# UsbPowerSupply.net
KiCad netlist of a schematic drawn in EAGLE
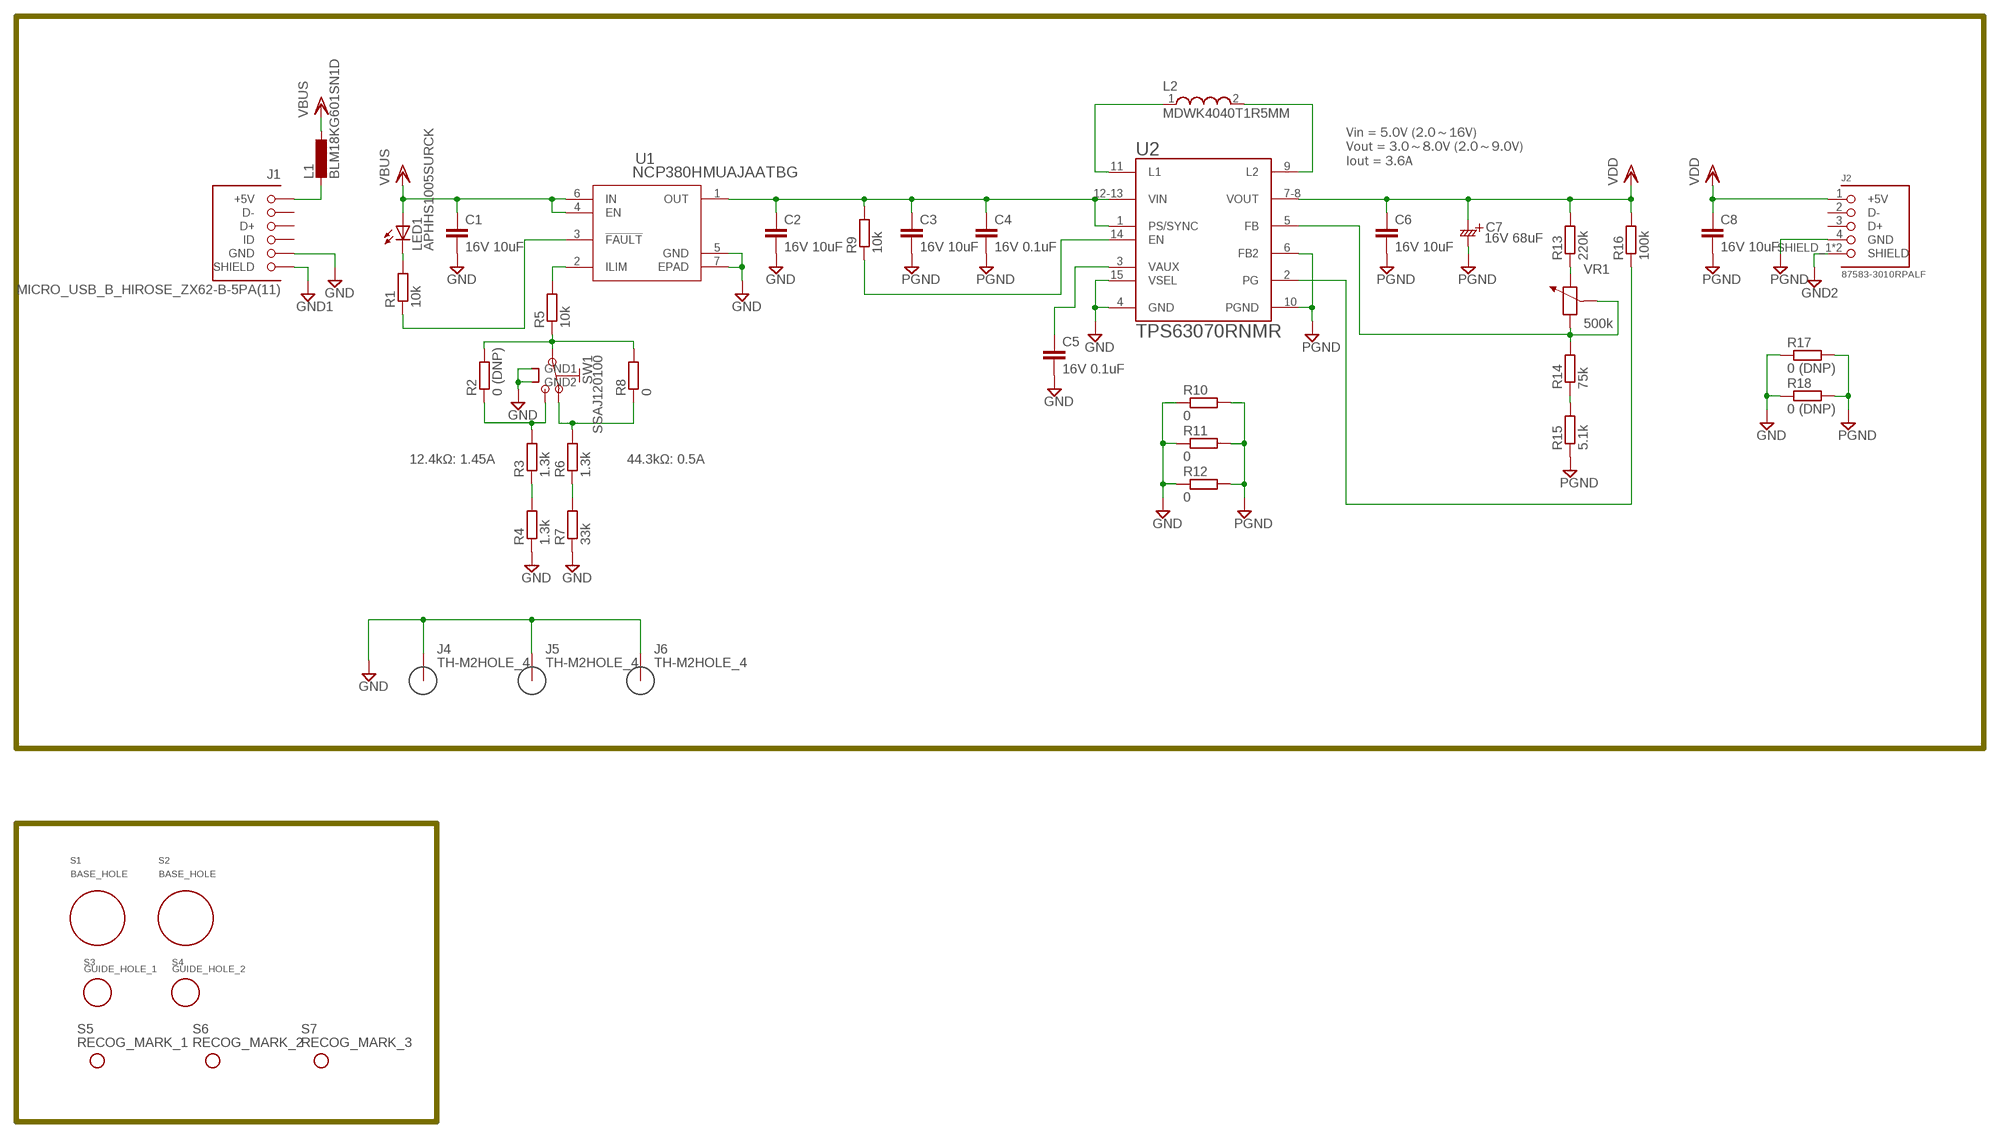
[diagram p0: schematic, sheet 1]

(export (version "E")
  (design (tool "Eeschema 10.0.6"))
  (components
    (comp (ref "C1")
      (value "16V 10uF")
      (footprint "eagle-import:C0603M")
      (libsource (lib "eagle-import") (part "C-EUC0603M"))
    )
    (comp (ref "C2")
      (value "16V 10uF")
      (footprint "eagle-import:C0603M")
      (libsource (lib "eagle-import") (part "C-EUC0603M"))
    )
    (comp (ref "C3")
      (value "16V 10uF")
      (footprint "eagle-import:C0603M")
      (libsource (lib "eagle-import") (part "C-EUC0603M"))
    )
    (comp (ref "C4")
      (value "16V 0.1uF")
      (footprint "eagle-import:C0402M")
      (libsource (lib "eagle-import") (part "C-EUC0402M"))
    )
    (comp (ref "C5")
      (value "16V 0.1uF")
      (footprint "eagle-import:C0402M")
      (libsource (lib "eagle-import") (part "C-EUC0402M"))
    )
    (comp (ref "C6")
      (value "16V 10uF")
      (footprint "eagle-import:C0603M")
      (libsource (lib "eagle-import") (part "C-EUC0603M"))
    )
    (comp (ref "C7")
      (value "16V 68uF")
      (footprint "eagle-import:EEFCX_7343")
      (libsource (lib "eagle-import") (part "EEFCX"))
    )
    (comp (ref "C8")
      (value "16V 10uF")
      (footprint "eagle-import:C0603M")
      (libsource (lib "eagle-import") (part "C-EUC0603M"))
    )
    (comp (ref "J1")
      (value "MICRO_USB_B_HIROSE_ZX62-B-5PA(11)")
      (footprint "eagle-import:USB_MICRO_B-HIROSE-ZX62-B-5PA(11)")
      (libsource (lib "eagle-import") (part "MICRO_USB_B_HIROSE_ZX62-B-5PA(11)"))
    )
    (comp (ref "J2")
      (value "87583-3010RPALF")
      (footprint "eagle-import:USB_A_FEMALE")
      (libsource (lib "eagle-import") (part "87583-3010RPALF"))
    )
    (comp (ref "J4")
      (value "TH-M2HOLE_4")
      (footprint "eagle-import:HOLE_M2_PHI4")
      (libsource (lib "eagle-import") (part "TH-M2HOLE_4"))
    )
    (comp (ref "J5")
      (value "TH-M2HOLE_4")
      (footprint "eagle-import:HOLE_M2_PHI4")
      (libsource (lib "eagle-import") (part "TH-M2HOLE_4"))
    )
    (comp (ref "J6")
      (value "TH-M2HOLE_4")
      (footprint "eagle-import:HOLE_M2_PHI4")
      (libsource (lib "eagle-import") (part "TH-M2HOLE_4"))
    )
    (comp (ref "L1")
      (value "BLM18KG601SN1D")
      (footprint "eagle-import:L1608")
      (libsource (lib "eagle-import") (part "L-EUL1608"))
    )
    (comp (ref "L2")
      (value "MDWK4040T1R5MM")
      (footprint "eagle-import:WE-MAPI_4020")
      (libsource (lib "eagle-import") (part "WE-MAPI4020"))
    )
    (comp (ref "LED1")
      (value "APHHS1005SURCK")
      (footprint "eagle-import:1005")
      (libsource (lib "eagle-import") (part "LED"))
    )
    (comp (ref "R1")
      (value "10k")
      (footprint "eagle-import:R0402R")
      (libsource (lib "eagle-import") (part "R-EU_R0402R"))
    )
    (comp (ref "R2")
      (value "0 (DNP)")
      (footprint "eagle-import:R0402R")
      (libsource (lib "eagle-import") (part "R-EU_R0402R"))
    )
    (comp (ref "R3")
      (value "1.3k")
      (footprint "eagle-import:R0402R")
      (libsource (lib "eagle-import") (part "R-EU_R0402R"))
    )
    (comp (ref "R4")
      (value "1.3k")
      (footprint "eagle-import:R0402R")
      (libsource (lib "eagle-import") (part "R-EU_R0402R"))
    )
    (comp (ref "R5")
      (value "10k")
      (footprint "eagle-import:R0402R")
      (libsource (lib "eagle-import") (part "R-EU_R0402R"))
    )
    (comp (ref "R6")
      (value "1.3k")
      (footprint "eagle-import:R0402R")
      (libsource (lib "eagle-import") (part "R-EU_R0402R"))
    )
    (comp (ref "R7")
      (value "33k")
      (footprint "eagle-import:R0402R")
      (libsource (lib "eagle-import") (part "R-EU_R0402R"))
    )
    (comp (ref "R8")
      (value "0")
      (footprint "eagle-import:R0402R")
      (libsource (lib "eagle-import") (part "R-EU_R0402R"))
    )
    (comp (ref "R9")
      (value "10k")
      (footprint "eagle-import:R0402R")
      (libsource (lib "eagle-import") (part "R-EU_R0402R"))
    )
    (comp (ref "R10")
      (value "0")
      (footprint "eagle-import:R0402R")
      (libsource (lib "eagle-import") (part "R-EU_R0402R"))
    )
    (comp (ref "R11")
      (value "0")
      (footprint "eagle-import:R0402R")
      (libsource (lib "eagle-import") (part "R-EU_R0402R"))
    )
    (comp (ref "R12")
      (value "0")
      (footprint "eagle-import:R0402R")
      (libsource (lib "eagle-import") (part "R-EU_R0402R"))
    )
    (comp (ref "R13")
      (value "220k")
      (footprint "eagle-import:R0402R")
      (libsource (lib "eagle-import") (part "R-EU_R0402R"))
    )
    (comp (ref "R14")
      (value "75k")
      (footprint "eagle-import:R0402R")
      (libsource (lib "eagle-import") (part "R-EU_R0402R"))
    )
    (comp (ref "R15")
      (value "5.1k")
      (footprint "eagle-import:R0402R")
      (libsource (lib "eagle-import") (part "R-EU_R0402R"))
    )
    (comp (ref "R16")
      (value "100k")
      (footprint "eagle-import:R0402R")
      (libsource (lib "eagle-import") (part "R-EU_R0402R"))
    )
    (comp (ref "R17")
      (value "0 (DNP)")
      (footprint "eagle-import:R0402R")
      (libsource (lib "eagle-import") (part "R-EU_R0402R"))
    )
    (comp (ref "R18")
      (value "0 (DNP)")
      (footprint "eagle-import:R0402R")
      (libsource (lib "eagle-import") (part "R-EU_R0402R"))
    )
    (comp (ref "S1")
      (value "BASE_HOLE")
      (footprint "eagle-import:BASE_HOLE")
      (libsource (lib "eagle-import") (part "BASE_HOLE"))
    )
    (comp (ref "S2")
      (value "BASE_HOLE")
      (footprint "eagle-import:BASE_HOLE")
      (libsource (lib "eagle-import") (part "BASE_HOLE"))
    )
    (comp (ref "S3")
      (value "GUIDE_HOLE_1")
      (footprint "eagle-import:GUIDE_HOLE")
      (libsource (lib "eagle-import") (part "GUIDE_HOLE_1"))
    )
    (comp (ref "S4")
      (value "GUIDE_HOLE_2")
      (footprint "eagle-import:GUIDE_HOLE")
      (libsource (lib "eagle-import") (part "GUIDE_HOLE_2"))
    )
    (comp (ref "S5")
      (value "RECOG_MARK_1")
      (footprint "eagle-import:RECOG_MARK")
      (libsource (lib "eagle-import") (part "RECOG_MARK_1"))
    )
    (comp (ref "S6")
      (value "RECOG_MARK_2")
      (footprint "eagle-import:RECOG_MARK")
      (libsource (lib "eagle-import") (part "RECOG_MARK_2"))
    )
    (comp (ref "S7")
      (value "RECOG_MARK_3")
      (footprint "eagle-import:RECOG_MARK")
      (libsource (lib "eagle-import") (part "RECOG_MARK_3"))
    )
    (comp (ref "SW1")
      (value "SSAJ120100")
      (footprint "eagle-import:SSAJ120100")
      (libsource (lib "eagle-import") (part "SSAJ101002"))
    )
    (comp (ref "U1")
      (value "NCP380HMUAJAATBG")
      (footprint "eagle-import:NCP380_UDFN6")
      (libsource (lib "eagle-import") (part "NCP380HMUAJAATBG"))
    )
    (comp (ref "U2")
      (value "TPS63070RNMR")
      (footprint "eagle-import:QFN50P250X300X100-15N")
      (fields (field (name "DIGI-KEY_PART_NUMBER") "296-44874-1-ND") (field (name "MF") "Texas Instruments"))
      (libsource (lib "eagle-import") (part "TPS63070RNMR"))
    )
    (comp (ref "VR1")
      (value "500k")
      (footprint "eagle-import:VR_3006")
      (libsource (lib "eagle-import") (part "VR3006"))
    )
  )
  (nets
    (net (code "1") (name "GND") (class "Default")
      (node (ref "C1") (pin "2") (pinfunction "2_2") (pintype "passive"))
      (node (ref "C2") (pin "2") (pinfunction "2_2") (pintype "passive"))
      (node (ref "C5") (pin "2") (pinfunction "2_2") (pintype "passive"))
      (node (ref "J1") (pin "5") (pinfunction "GND_5") (pintype "bidirectional"))
      (node (ref "J4") (pin "P$1") (pinfunction "1_P$1") (pintype "bidirectional"))
      (node (ref "J5") (pin "P$1") (pinfunction "1_P$1") (pintype "bidirectional"))
      (node (ref "J6") (pin "P$1") (pinfunction "1_P$1") (pintype "bidirectional"))
      (node (ref "R10") (pin "1") (pinfunction "1_1") (pintype "passive"))
      (node (ref "R11") (pin "1") (pinfunction "1_1") (pintype "passive"))
      (node (ref "R12") (pin "1") (pinfunction "1_1") (pintype "passive"))
      (node (ref "R17") (pin "1") (pinfunction "1_1") (pintype "passive"))
      (node (ref "R18") (pin "1") (pinfunction "1_1") (pintype "passive"))
      (node (ref "R4") (pin "1") (pinfunction "1_1") (pintype "passive"))
      (node (ref "R7") (pin "1") (pinfunction "1_1") (pintype "passive"))
      (node (ref "SW1") (pin "4") (pinfunction "GND1_4") (pintype "power_in"))
      (node (ref "SW1") (pin "5") (pinfunction "GND2_5") (pintype "power_in"))
      (node (ref "U1") (pin "5") (pinfunction "GND_5") (pintype "power_in"))
      (node (ref "U1") (pin "7") (pinfunction "EPAD_7") (pintype "passive"))
      (node (ref "U2") (pin "15") (pinfunction "VSEL_15") (pintype "input"))
      (node (ref "U2") (pin "4") (pinfunction "GND_4") (pintype "power_in"))
    )
    (net (code "2") (name "GND1") (class "Default")
      (node (ref "J1") (pin "P$1") (pinfunction "SHIELD_P$1") (pintype "bidirectional"))
      (node (ref "J1") (pin "P$2") (pinfunction "SHIELD_P$2") (pintype "bidirectional"))
      (node (ref "J1") (pin "P$3") (pinfunction "SHIELD_P$3") (pintype "bidirectional"))
      (node (ref "J1") (pin "P$4") (pinfunction "SHIELD_P$4") (pintype "bidirectional"))
      (node (ref "J1") (pin "P$5") (pinfunction "SHIELD_P$5") (pintype "bidirectional"))
      (node (ref "J1") (pin "P$6") (pinfunction "SHIELD_P$6") (pintype "bidirectional"))
    )
    (net (code "3") (name "GND2") (class "Default")
      (node (ref "J2") (pin "SHIELD_1") (pinfunction "SHIELD_SHIELD_1") (pintype "bidirectional"))
      (node (ref "J2") (pin "SHIELD_2") (pinfunction "SHIELD_SHIELD_2") (pintype "bidirectional"))
    )
    (net (code "4") (name "Net-(J1-+5V)") (class "Default")
      (node (ref "J1") (pin "1") (pinfunction "+5V_1") (pintype "bidirectional"))
      (node (ref "L1") (pin "2") (pinfunction "2_2") (pintype "passive"))
    )
    (net (code "5") (name "Net-(LED1-PadK)") (class "Default")
      (node (ref "LED1") (pin "K") (pinfunction "K_K") (pintype "passive"))
      (node (ref "R1") (pin "2") (pinfunction "2_2") (pintype "passive"))
    )
    (net (code "6") (name "Net-(R2-Pad2)") (class "Default")
      (node (ref "R2") (pin "2") (pinfunction "2_2") (pintype "passive"))
      (node (ref "R5") (pin "1") (pinfunction "1_1") (pintype "passive"))
      (node (ref "R8") (pin "2") (pinfunction "2_2") (pintype "passive"))
      (node (ref "SW1") (pin "2") (pinfunction "2_2") (pintype "passive"))
    )
    (net (code "7") (name "Net-(R3-Pad1)") (class "Default")
      (node (ref "R3") (pin "1") (pinfunction "1_1") (pintype "passive"))
      (node (ref "R4") (pin "2") (pinfunction "2_2") (pintype "passive"))
    )
    (net (code "8") (name "Net-(R6-Pad1)") (class "Default")
      (node (ref "R6") (pin "1") (pinfunction "1_1") (pintype "passive"))
      (node (ref "R7") (pin "2") (pinfunction "2_2") (pintype "passive"))
    )
    (net (code "9") (name "Net-(R13-Pad1)") (class "Default")
      (node (ref "R13") (pin "1") (pinfunction "1_1") (pintype "passive"))
      (node (ref "VR1") (pin "1") (pinfunction "1_1") (pintype "passive"))
    )
    (net (code "10") (name "Net-(R14-Pad1)") (class "Default")
      (node (ref "R14") (pin "1") (pinfunction "1_1") (pintype "passive"))
      (node (ref "R15") (pin "2") (pinfunction "2_2") (pintype "passive"))
    )
    (net (code "11") (name "Net-(SW1-1)") (class "Default")
      (node (ref "R6") (pin "2") (pinfunction "2_2") (pintype "passive"))
      (node (ref "R8") (pin "1") (pinfunction "1_1") (pintype "passive"))
      (node (ref "SW1") (pin "3") (pinfunction "1_3") (pintype "passive"))
    )
    (net (code "12") (name "Net-(SW1-3)") (class "Default")
      (node (ref "R2") (pin "1") (pinfunction "1_1") (pintype "passive"))
      (node (ref "R3") (pin "2") (pinfunction "2_2") (pintype "passive"))
      (node (ref "SW1") (pin "1") (pinfunction "3_1") (pintype "passive"))
    )
    (net (code "13") (name "Net-(U1-ILIM)") (class "Default")
      (node (ref "R5") (pin "2") (pinfunction "2_2") (pintype "passive"))
      (node (ref "U1") (pin "2") (pinfunction "ILIM_2") (pintype "output"))
    )
    (net (code "14") (name "Net-(U1-OUT)") (class "Default")
      (node (ref "C2") (pin "1") (pinfunction "1_1") (pintype "passive"))
      (node (ref "C3") (pin "1") (pinfunction "1_1") (pintype "passive"))
      (node (ref "C4") (pin "1") (pinfunction "1_1") (pintype "passive"))
      (node (ref "R9") (pin "2") (pinfunction "2_2") (pintype "passive"))
      (node (ref "U1") (pin "1") (pinfunction "OUT_1") (pintype "output"))
      (node (ref "U2") (pin "1") (pinfunction "PS/SYNC_1") (pintype "input"))
      (node (ref "U2") (pin "12-13") (pinfunction "VIN_12-13") (pintype "input"))
    )
    (net (code "15") (name "Net-(U1-~{FAULT})") (class "Default")
      (node (ref "R1") (pin "1") (pinfunction "1_1") (pintype "passive"))
      (node (ref "U1") (pin "3") (pinfunction "~{FAULT}_3") (pintype "output"))
    )
    (net (code "16") (name "Net-(U2-EN)") (class "Default")
      (node (ref "R9") (pin "1") (pinfunction "1_1") (pintype "passive"))
      (node (ref "U2") (pin "14") (pinfunction "EN_14") (pintype "input"))
    )
    (net (code "17") (name "Net-(U2-FB)") (class "Default")
      (node (ref "R14") (pin "2") (pinfunction "2_2") (pintype "passive"))
      (node (ref "U2") (pin "5") (pinfunction "FB_5") (pintype "input"))
      (node (ref "VR1") (pin "2") (pinfunction "CENTER_2") (pintype "passive"))
      (node (ref "VR1") (pin "3") (pinfunction "2_3") (pintype "passive"))
    )
    (net (code "18") (name "Net-(U2-L1)") (class "Default")
      (node (ref "L2") (pin "1") (pinfunction "1_1") (pintype "passive"))
      (node (ref "U2") (pin "11") (pinfunction "L1_11") (pintype "input"))
    )
    (net (code "19") (name "Net-(U2-L2)") (class "Default")
      (node (ref "L2") (pin "2") (pinfunction "2_2") (pintype "passive"))
      (node (ref "U2") (pin "9") (pinfunction "L2_9") (pintype "input"))
    )
    (net (code "20") (name "Net-(U2-PG)") (class "Default")
      (node (ref "R16") (pin "1") (pinfunction "1_1") (pintype "passive"))
      (node (ref "U2") (pin "2") (pinfunction "PG_2") (pintype "output"))
    )
    (net (code "21") (name "Net-(U2-VAUX)") (class "Default")
      (node (ref "C5") (pin "1") (pinfunction "1_1") (pintype "passive"))
      (node (ref "U2") (pin "3") (pinfunction "VAUX_3") (pintype "output"))
    )
    (net (code "22") (name "PGND") (class "Default")
      (node (ref "C3") (pin "2") (pinfunction "2_2") (pintype "passive"))
      (node (ref "C4") (pin "2") (pinfunction "2_2") (pintype "passive"))
      (node (ref "C6") (pin "2") (pinfunction "2_2") (pintype "passive"))
      (node (ref "C7") (pin "MINUS") (pinfunction "MINUS_MINUS") (pintype "passive"))
      (node (ref "C8") (pin "2") (pinfunction "2_2") (pintype "passive"))
      (node (ref "J2") (pin "4") (pinfunction "GND_4") (pintype "bidirectional"))
      (node (ref "R10") (pin "2") (pinfunction "2_2") (pintype "passive"))
      (node (ref "R11") (pin "2") (pinfunction "2_2") (pintype "passive"))
      (node (ref "R12") (pin "2") (pinfunction "2_2") (pintype "passive"))
      (node (ref "R15") (pin "1") (pinfunction "1_1") (pintype "passive"))
      (node (ref "R17") (pin "2") (pinfunction "2_2") (pintype "passive"))
      (node (ref "R18") (pin "2") (pinfunction "2_2") (pintype "passive"))
      (node (ref "U2") (pin "10") (pinfunction "PGND_10") (pintype "power_in"))
      (node (ref "U2") (pin "6") (pinfunction "FB2_6") (pintype "output"))
    )
    (net (code "23") (name "VBUS") (class "Default")
      (node (ref "C1") (pin "1") (pinfunction "1_1") (pintype "passive"))
      (node (ref "L1") (pin "1") (pinfunction "1_1") (pintype "passive"))
      (node (ref "LED1") (pin "A") (pinfunction "A_A") (pintype "passive"))
      (node (ref "U1") (pin "4") (pinfunction "EN_4") (pintype "input"))
      (node (ref "U1") (pin "6") (pinfunction "IN_6") (pintype "input"))
    )
    (net (code "24") (name "VDD") (class "Default")
      (node (ref "C6") (pin "1") (pinfunction "1_1") (pintype "passive"))
      (node (ref "C7") (pin "PLUS") (pinfunction "PLUS_PLUS") (pintype "passive"))
      (node (ref "C8") (pin "1") (pinfunction "1_1") (pintype "passive"))
      (node (ref "J2") (pin "1") (pinfunction "+5V_1") (pintype "bidirectional"))
      (node (ref "R13") (pin "2") (pinfunction "2_2") (pintype "passive"))
      (node (ref "R16") (pin "2") (pinfunction "2_2") (pintype "passive"))
      (node (ref "U2") (pin "7-8") (pinfunction "VOUT_7-8") (pintype "output"))
    )
    (net (code "25") (name "unconnected-(J1-D+-Pad3)") (class "Default")
      (node (ref "J1") (pin "3") (pinfunction "D+_3") (pintype "bidirectional"))
    )
    (net (code "26") (name "unconnected-(J1-D--Pad2)") (class "Default")
      (node (ref "J1") (pin "2") (pinfunction "D-_2") (pintype "bidirectional"))
    )
    (net (code "27") (name "unconnected-(J1-ID-Pad4)") (class "Default")
      (node (ref "J1") (pin "4") (pinfunction "ID_4") (pintype "bidirectional"))
    )
    (net (code "28") (name "unconnected-(J2-D+-Pad3)") (class "Default")
      (node (ref "J2") (pin "3") (pinfunction "D+_3") (pintype "bidirectional"))
    )
    (net (code "29") (name "unconnected-(J2-D--Pad2)") (class "Default")
      (node (ref "J2") (pin "2") (pinfunction "D-_2") (pintype "bidirectional"))
    )
  )
)
